# POWER.net
KiCad netlist of a schematic drawn in Altium Designer
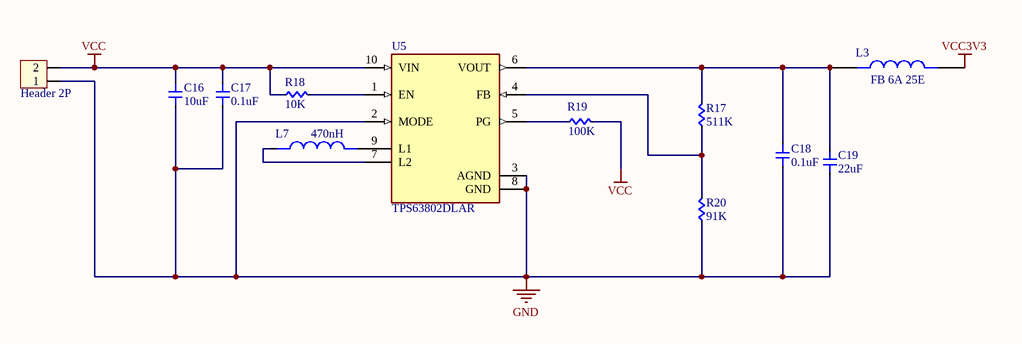
[diagram p0: POWER.SchDoc]

(export (version "E")
  (design (tool "Eeschema 10.0.6"))
  (components
    (comp (ref "C16")
      (value "10uF")
      (footprint "Cap 0805")
      (description "Capacitor SMD 0805")
      (libsource (lib "Altium_Lib_by_KhueNguyenCreator") (part "Cap 0805"))
    )
    (comp (ref "C17")
      (value "0.1uF")
      (footprint "Cap 0805")
      (description "Capacitor SMD 0805")
      (libsource (lib "Altium_Lib_by_KhueNguyenCreator") (part "Cap 0805"))
    )
    (comp (ref "C18")
      (value "0.1uF")
      (footprint "Cap 0805")
      (description "Capacitor SMD 0805")
      (libsource (lib "Altium_Lib_by_KhueNguyenCreator") (part "Cap 0805"))
    )
    (comp (ref "C19")
      (value "22uF")
      (footprint "Cap 0805")
      (description "Capacitor SMD 0805")
      (libsource (lib "Altium_Lib_by_KhueNguyenCreator") (part "Cap 0805"))
    )
    (comp (ref "H1")
      (value "Header 2P")
      (footprint "XH2.54M-2")
      (description "Cắm")
      (libsource (lib "Altium_Lib_by_KhueNguyenCreator") (part "Header 2P 2.54 Duc Thang"))
    )
    (comp (ref "L3")
      (value "FB 6A 25E")
      (footprint "INDC2012X145N")
      (description "22 ÂµH Shielded Multilayer Inductor 300 mA 670mOhm 0805 (2012 Metric)")
      (fields (field (name "MF") "TDK") (field (name "MP") "MLZ2012N220LT000"))
      (libsource (lib "Cuoncam22uh") (part "MLZ2012N220LT000"))
    )
    (comp (ref "L7")
      (value "470nH")
      (footprint "CUON CAM SMD 0530")
      (description "SMD 0530")
      (fields (field (name "MP") "FDV0530-H-1R5M=P3"))
      (libsource (lib "Altium_Lib_by_KhueNguyenCreator") (part "Cuon Cam SMD 0530"))
    )
    (comp (ref "R17")
      (value "511K")
      (footprint "RES 0805")
      (description "RES SMD 0805")
      (fields
        (field (name "MANUFACTURER") "Vishay Dale")
        (field (name "MANUFACTURER PART NUMBER") "CRCW040210K0FKED")
      )
      (libsource (lib "Altium_Lib_by_KhueNguyenCreator") (part "RES 0805"))
    )
    (comp (ref "R18")
      (value "10K")
      (footprint "RES 0805")
      (description "RES SMD 0805")
      (fields
        (field (name "MANUFACTURER") "Vishay Dale")
        (field (name "MANUFACTURER PART NUMBER") "CRCW040210K0FKED")
      )
      (libsource (lib "Altium_Lib_by_KhueNguyenCreator") (part "RES 0805"))
    )
    (comp (ref "R19")
      (value "100K")
      (footprint "RES 0805")
      (description "RES SMD 0805")
      (fields
        (field (name "MANUFACTURER") "Vishay Dale")
        (field (name "MANUFACTURER PART NUMBER") "CRCW040210K0FKED")
      )
      (libsource (lib "Altium_Lib_by_KhueNguyenCreator") (part "RES 0805"))
    )
    (comp (ref "R20")
      (value "91K")
      (footprint "RES 0805")
      (description "RES SMD 0805")
      (fields
        (field (name "MANUFACTURER") "Vishay Dale")
        (field (name "MANUFACTURER PART NUMBER") "CRCW040210K0FKED")
      )
      (libsource (lib "Altium_Lib_by_KhueNguyenCreator") (part "RES 0805"))
    )
    (comp (ref "U5")
      (value "TPS63802DLAR")
      (footprint "VREG_TPS63802DLAR")
      (description "2-A, high-efficient, 11-ÂµA quiescent current buck-boost converter in QFN/DFN package")
      (fields (field (name "MF") "Texas Instruments"))
      (libsource (lib "TPS63802DLAR") (part "TPS63802DLAR"))
    )
  )
  (nets
    (net (code "1") (name "GND") (class "Default")
      (node (ref "C16") (pin "2") (pinfunction "2_2") (pintype "passive"))
      (node (ref "C17") (pin "2") (pinfunction "2_2") (pintype "passive"))
      (node (ref "C18") (pin "2") (pinfunction "2_2") (pintype "passive"))
      (node (ref "C19") (pin "2") (pinfunction "2_2") (pintype "passive"))
      (node (ref "H1") (pin "1") (pinfunction "1_1") (pintype "passive"))
      (node (ref "R20") (pin "1") (pinfunction "1_1") (pintype "passive"))
      (node (ref "U5") (pin "2") (pinfunction "MODE_2") (pintype "input"))
      (node (ref "U5") (pin "3") (pinfunction "AGND_3") (pintype "power_in"))
      (node (ref "U5") (pin "8") (pinfunction "GND_8") (pintype "power_in"))
    )
    (net (code "2") (name "Net-(U5-EN)") (class "Default")
      (node (ref "R18") (pin "2") (pinfunction "2_2") (pintype "passive"))
      (node (ref "U5") (pin "1") (pinfunction "EN_1") (pintype "input"))
    )
    (net (code "3") (name "Net-(U5-FB)") (class "Default")
      (node (ref "R17") (pin "1") (pinfunction "1_1") (pintype "passive"))
      (node (ref "R20") (pin "2") (pinfunction "2_2") (pintype "passive"))
      (node (ref "U5") (pin "4") (pinfunction "FB_4") (pintype "input"))
    )
    (net (code "4") (name "Net-(U5-L1)") (class "Default")
      (node (ref "L7") (pin "2") (pinfunction "2_2") (pintype "passive"))
      (node (ref "U5") (pin "9") (pinfunction "L1_9") (pintype "passive"))
    )
    (net (code "5") (name "Net-(U5-L2)") (class "Default")
      (node (ref "L7") (pin "1") (pinfunction "1_1") (pintype "passive"))
      (node (ref "U5") (pin "7") (pinfunction "L2_7") (pintype "passive"))
    )
    (net (code "6") (name "Net-(U5-PG)") (class "Default")
      (node (ref "R19") (pin "1") (pinfunction "1_1") (pintype "passive"))
      (node (ref "U5") (pin "5") (pinfunction "PG_5") (pintype "output"))
    )
    (net (code "7") (name "Net-(U5-VOUT)") (class "Default")
      (node (ref "C18") (pin "1") (pinfunction "1_1") (pintype "passive"))
      (node (ref "C19") (pin "1") (pinfunction "1_1") (pintype "passive"))
      (node (ref "L3") (pin "1") (pinfunction "1_1") (pintype "passive"))
      (node (ref "R17") (pin "2") (pinfunction "2_2") (pintype "passive"))
      (node (ref "U5") (pin "6") (pinfunction "VOUT_6") (pintype "output"))
    )
    (net (code "8") (name "VCC") (class "Default")
      (node (ref "C16") (pin "1") (pinfunction "1_1") (pintype "passive"))
      (node (ref "C17") (pin "1") (pinfunction "1_1") (pintype "passive"))
      (node (ref "H1") (pin "2") (pinfunction "2_2") (pintype "passive"))
      (node (ref "R18") (pin "1") (pinfunction "1_1") (pintype "passive"))
      (node (ref "R19") (pin "2") (pinfunction "2_2") (pintype "passive"))
      (node (ref "U5") (pin "10") (pinfunction "VIN_10") (pintype "input"))
    )
    (net (code "9") (name "VCC3V3") (class "Default")
      (node (ref "L3") (pin "2") (pinfunction "2_2") (pintype "passive"))
    )
  )
)
